# Power_Supply.net
KiCad netlist of a schematic drawn in Altium Designer
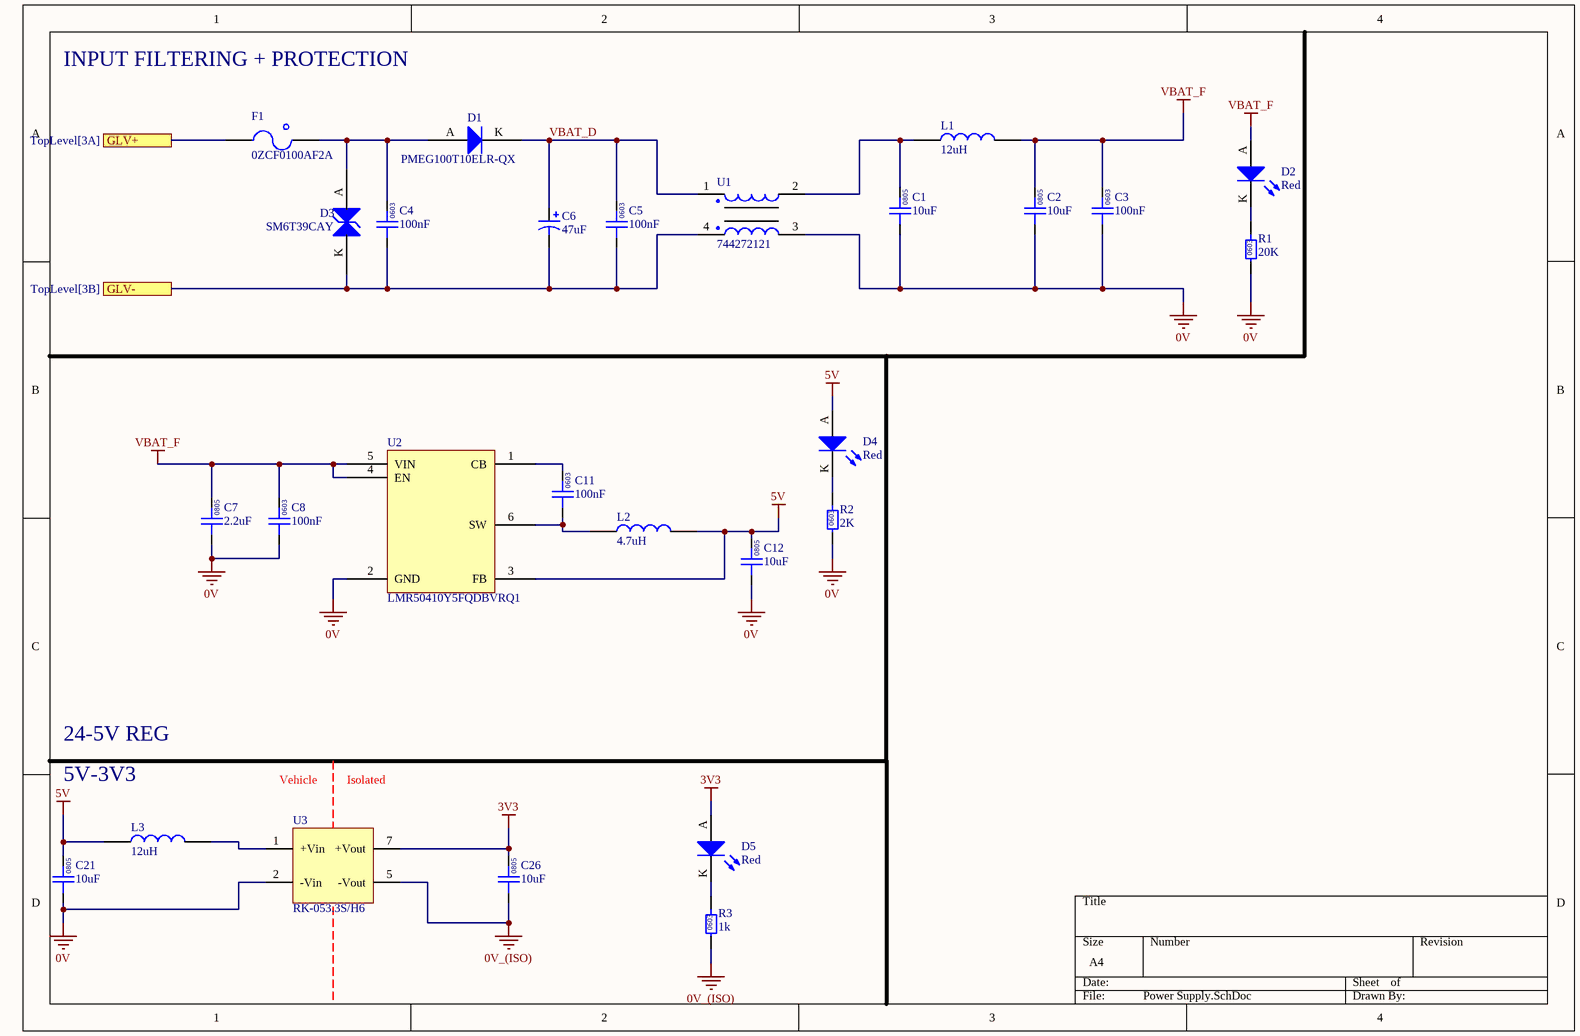
[diagram p0: Power Supply.SchDoc]

(export (version "E")
  (design (tool "Eeschema 10.0.6"))
  (components
    (comp (ref "C1")
      (value "10uF")
      (footprint "0805")
      (fields
        (field (name "PART NUMBER") "GRM21BR6YA106KE43L")
        (field (name "MANUFACTURER") "muRata")
        (field (name "TOLERANCE") "10%")
      )
      (libsource (lib "ts_standard_library") (part "Capacitor 0805"))
    )
    (comp (ref "C2")
      (value "10uF")
      (footprint "0805")
      (fields
        (field (name "PART NUMBER") "GRM21BR6YA106KE43L")
        (field (name "MANUFACTURER") "muRata")
        (field (name "TOLERANCE") "10%")
      )
      (libsource (lib "ts_standard_library") (part "Capacitor 0805"))
    )
    (comp (ref "C3")
      (value "100nF")
      (footprint "0603")
      (fields
        (field (name "PART NUMBER") "GCM188L81H104KA57D")
        (field (name "MANUFACTURER") "muRata")
        (field (name "TOLERANCE") "±10%")
      )
      (libsource (lib "ts_standard_library") (part "Capacitor 0603"))
    )
    (comp (ref "C4")
      (value "100nF")
      (footprint "0603")
      (fields
        (field (name "PART NUMBER") "GCM188L81H104KA57D")
        (field (name "MANUFACTURER") "muRata")
        (field (name "TOLERANCE") "±10%")
      )
      (libsource (lib "ts_standard_library") (part "Capacitor 0603"))
    )
    (comp (ref "C5")
      (value "100nF")
      (footprint "0603")
      (fields
        (field (name "PART NUMBER") "GCM188L81H104KA57D")
        (field (name "MANUFACTURER") "muRata")
        (field (name "TOLERANCE") "±10%")
      )
      (libsource (lib "ts_standard_library") (part "Capacitor 0603"))
    )
    (comp (ref "C6")
      (value "47uF")
      (footprint "CHEMI-CON ELCO")
      (fields (field (name "PART NUMBER") "HHXA350ARA470MF61G"))
      (libsource (lib "ts_standard_library") (part "Capacitor (Polarised)"))
    )
    (comp (ref "C7")
      (value "2.2uF")
      (footprint "0805")
      (fields
        (field (name "PART NUMBER") "GRM21BR61A226ME51L")
        (field (name "MANUFACTURER") "muRata")
        (field (name "TOLERANCE") "20%")
      )
      (libsource (lib "ts_standard_library") (part "Capacitor 0805"))
    )
    (comp (ref "C8")
      (value "100nF")
      (footprint "0603")
      (fields
        (field (name "PART NUMBER") "GCM188L81H104KA57D")
        (field (name "MANUFACTURER") "muRata")
        (field (name "TOLERANCE") "±10%")
      )
      (libsource (lib "ts_standard_library") (part "Capacitor 0603"))
    )
    (comp (ref "C11")
      (value "100nF")
      (footprint "0603")
      (fields
        (field (name "PART NUMBER") "GCM188L81H104KA57D")
        (field (name "MANUFACTURER") "muRata")
        (field (name "TOLERANCE") "±10%")
      )
      (libsource (lib "ts_standard_library") (part "Capacitor 0603"))
    )
    (comp (ref "C12")
      (value "10uF")
      (footprint "0805")
      (fields
        (field (name "PART NUMBER") "GRM21BR6YA106KE43L")
        (field (name "MANUFACTURER") "muRata")
        (field (name "TOLERANCE") "10%")
      )
      (libsource (lib "ts_standard_library") (part "Capacitor 0805"))
    )
    (comp (ref "C21")
      (value "10uF")
      (footprint "0805")
      (fields
        (field (name "PART NUMBER") "GRM21BR6YA106KE43L")
        (field (name "MANUFACTURER") "muRata")
        (field (name "TOLERANCE") "10%")
      )
      (libsource (lib "ts_standard_library") (part "Capacitor 0805"))
    )
    (comp (ref "C26")
      (value "10uF")
      (footprint "0805")
      (fields
        (field (name "PART NUMBER") "GRM21BR6YA106KE43L")
        (field (name "MANUFACTURER") "muRata")
        (field (name "TOLERANCE") "10%")
      )
      (libsource (lib "ts_standard_library") (part "Capacitor 0805"))
    )
    (comp (ref "D1")
      (value "PMEG100T10ELR-QX")
      (footprint "SODFL350X110-2N")
      (description "Diode 100 V 1A Surface Mount SOD-123W")
      (libsource (lib "Team Swinburne") (part "PMEG100T10ELR-QX"))
    )
    (comp (ref "D2")
      (value "Red")
      (footprint "0805 LED")
      (description "Red LED Indication - Discrete 1.75V 0805 (2012 Metric)")
      (fields (field (name "PART NUMBER") "SML-210LTT86") (field (name "MANUFACTURER") "ROHM Semiconductor"))
      (libsource (lib "ts_standard_library") (part "LED"))
    )
    (comp (ref "D3")
      (value "SM6T39CAY")
      (footprint "SM6T39CAY-Footprint-1")
      (description "TVS Diode Single Bi-Dir 33.3V 600W Automotive 2-Pin SMB T/R / TVS DIODE 33.3VWM 69.7VC SMB")
      (libsource (lib "Team Swinburne") (part "SM6T39CAY-Symbol"))
    )
    (comp (ref "D4")
      (value "Red")
      (footprint "0805 LED")
      (description "Red LED Indication - Discrete 1.75V 0805 (2012 Metric)")
      (fields (field (name "PART NUMBER") "SML-210LTT86") (field (name "MANUFACTURER") "ROHM Semiconductor"))
      (libsource (lib "ts_standard_library") (part "LED"))
    )
    (comp (ref "D5")
      (value "Red")
      (footprint "0805 LED")
      (description "Red LED Indication - Discrete 1.75V 0805 (2012 Metric)")
      (fields (field (name "PART NUMBER") "SML-210LTT86") (field (name "MANUFACTURER") "ROHM Semiconductor"))
      (libsource (lib "ts_standard_library") (part "LED"))
    )
    (comp (ref "F1")
      (value "0ZCF0100AF2A")
      (footprint "2920")
      (description "PTC RESET FUSE 60V 1A 292")
      (fields
        (field (name "MANUFACTURER") "Littelfuse Inc.")
        (field (name "DIGIKEY PART NUMBER") "507-2070-1-ND")
      )
      (libsource (lib "ts_standard_library") (part "PTC Fuse"))
    )
    (comp (ref "L1")
      (value "12uH")
      (footprint "1812")
      (fields
        (field (name "PART NUMBER") "RLS-126")
        (field (name "MANUFACTURER") "Recom")
        (field (name "TOLERANCE") "0.2")
      )
      (libsource (lib "ts_standard_library") (part "Inductor"))
    )
    (comp (ref "L2")
      (value "4.7uH")
      (footprint "SRN3015TA-4R7M")
      (fields
        (field (name "PART NUMBER") "SRN4018-4R7M")
        (field (name "MANUFACTURER") "Bourns")
        (field (name "TOLERANCE") "0.2")
      )
      (libsource (lib "ts_standard_library") (part "Inductor"))
    )
    (comp (ref "L3")
      (value "12uH")
      (footprint "1812")
      (fields
        (field (name "PART NUMBER") "RLS-126")
        (field (name "MANUFACTURER") "Recom")
        (field (name "TOLERANCE") "0.2")
      )
      (libsource (lib "ts_standard_library") (part "Inductor"))
    )
    (comp (ref "R1")
      (value "20K")
      (footprint "0603")
      (fields
        (field (name "PART NUMBER") "RC0603FR-0720KL")
        (field (name "MANUFACTURER") "YAGEO")
        (field (name "TOLERANCE") "0.01")
      )
      (libsource (lib "ts_standard_library") (part "Resistor 0603"))
    )
    (comp (ref "R2")
      (value "2K")
      (footprint "0603")
      (fields
        (field (name "PART NUMBER") "RC0603FR-072KL")
        (field (name "MANUFACTURER") "YAGEO")
        (field (name "TOLERANCE") "0.01")
      )
      (libsource (lib "ts_standard_library") (part "Resistor 0603"))
    )
    (comp (ref "R3")
      (value "1k")
      (footprint "0603")
      (fields
        (field (name "PART NUMBER") "RC0603FR-071KL")
        (field (name "MANUFACTURER") "YAGEO")
        (field (name "TOLERANCE") "0.01")
      )
      (libsource (lib "ts_standard_library") (part "Resistor 0603"))
    )
    (comp (ref "U1")
      (value "744272121")
      (footprint "Wurth 4-PC Pad")
      (fields
        (field (name "MANUFACTURER") "Wurth Electronics Inc")
        (field (name "DIGIKEY PART NUMBER") "732-1489-1-ND")
      )
      (libsource (lib "ts_standard_library") (part "CM Choke"))
    )
    (comp (ref "U2")
      (value "LMR50410Y5FQDBVRQ1")
      (footprint "TI-SOT23-6")
      (description "IC REG BUCK 5V 1A SOT23-6")
      (fields (field (name "PART NUMBER") "LMR50410-Q1") (field (name "MANUFACTURER") "Texas Instruments"))
      (libsource (lib "ts_standard_library") (part "LMR50410Y5FQDBVRQ1"))
    )
    (comp (ref "U3")
      (value "RK-053.3S/H6")
      (footprint "RK-053.3S/H6")
      (description "DC DC CONVERTER 3.3V 1W")
      (fields (field (name "MANUFACTURER") "Recom"))
      (libsource (lib "ts_standard_library") (part "RK-053.3S/H6"))
    )
  )
  (nets
    (net (code "1") (name "/GLV+") (class "Default")
      (node (ref "F1") (pin "1") (pinfunction "1_1") (pintype "passive"))
    )
    (net (code "2") (name "/GLV-") (class "Default")
      (node (ref "C4") (pin "1") (pinfunction "1_1") (pintype "passive"))
      (node (ref "C5") (pin "1") (pinfunction "1_1") (pintype "passive"))
      (node (ref "C6") (pin "1") (pinfunction "1_1") (pintype "passive"))
      (node (ref "D3") (pin "K") (pintype "passive"))
      (node (ref "U1") (pin "4") (pinfunction "4_4") (pintype "passive"))
    )
    (net (code "3") (name "/VBAT_D") (class "Default")
      (node (ref "C5") (pin "2") (pinfunction "2_2") (pintype "passive"))
      (node (ref "C6") (pin "2") (pinfunction "2_2") (pintype "passive"))
      (node (ref "D1") (pin "K") (pintype "passive"))
      (node (ref "U1") (pin "1") (pinfunction "1_1") (pintype "passive"))
    )
    (net (code "4") (name "0V") (class "Default")
      (node (ref "C1") (pin "1") (pinfunction "1_1") (pintype "passive"))
      (node (ref "C12") (pin "1") (pinfunction "1_1") (pintype "passive"))
      (node (ref "C2") (pin "1") (pinfunction "1_1") (pintype "passive"))
      (node (ref "C21") (pin "1") (pinfunction "1_1") (pintype "passive"))
      (node (ref "C3") (pin "1") (pinfunction "1_1") (pintype "passive"))
      (node (ref "C7") (pin "1") (pinfunction "1_1") (pintype "passive"))
      (node (ref "C8") (pin "1") (pinfunction "1_1") (pintype "passive"))
      (node (ref "R1") (pin "1") (pinfunction "1_1") (pintype "passive"))
      (node (ref "R2") (pin "1") (pinfunction "1_1") (pintype "passive"))
      (node (ref "U1") (pin "3") (pinfunction "3_3") (pintype "power_in"))
      (node (ref "U2") (pin "2") (pinfunction "GND_2") (pintype "passive"))
      (node (ref "U3") (pin "2") (pinfunction "-Vin_2") (pintype "power_in"))
    )
    (net (code "5") (name "0V_(ISO)") (class "Default")
      (node (ref "C26") (pin "1") (pinfunction "1_1") (pintype "passive"))
      (node (ref "R3") (pin "1") (pinfunction "1_1") (pintype "passive"))
      (node (ref "U3") (pin "5") (pinfunction "-Vout_5") (pintype "power_in"))
    )
    (net (code "6") (name "3V3") (class "Default")
      (node (ref "C26") (pin "2") (pinfunction "2_2") (pintype "passive"))
      (node (ref "D5") (pin "A") (pinfunction "A_A") (pintype "passive"))
      (node (ref "U3") (pin "7") (pinfunction "+Vout_7") (pintype "power_in"))
    )
    (net (code "7") (name "5V") (class "Default")
      (node (ref "C12") (pin "2") (pinfunction "2_2") (pintype "passive"))
      (node (ref "C21") (pin "2") (pinfunction "2_2") (pintype "passive"))
      (node (ref "D4") (pin "A") (pinfunction "A_A") (pintype "passive"))
      (node (ref "L2") (pin "1") (pinfunction "1_1") (pintype "passive"))
      (node (ref "L3") (pin "2") (pinfunction "2_2") (pintype "passive"))
      (node (ref "U2") (pin "3") (pinfunction "FB_3") (pintype "passive"))
    )
    (net (code "8") (name "Net-(C1-Pad2)") (class "Default")
      (node (ref "C1") (pin "2") (pinfunction "2_2") (pintype "passive"))
      (node (ref "L1") (pin "2") (pinfunction "2_2") (pintype "passive"))
      (node (ref "U1") (pin "2") (pinfunction "2_2") (pintype "passive"))
    )
    (net (code "9") (name "Net-(C4-Pad2)") (class "Default")
      (node (ref "C4") (pin "2") (pinfunction "2_2") (pintype "passive"))
      (node (ref "D1") (pin "A") (pintype "passive"))
      (node (ref "D3") (pin "A") (pintype "passive"))
      (node (ref "F1") (pin "2") (pinfunction "2_2") (pintype "passive"))
    )
    (net (code "10") (name "Net-(D2-PadK)") (class "Default")
      (node (ref "D2") (pin "K") (pinfunction "K_K") (pintype "passive"))
      (node (ref "R1") (pin "2") (pinfunction "2_2") (pintype "passive"))
    )
    (net (code "11") (name "Net-(D4-PadK)") (class "Default")
      (node (ref "D4") (pin "K") (pinfunction "K_K") (pintype "passive"))
      (node (ref "R2") (pin "2") (pinfunction "2_2") (pintype "passive"))
    )
    (net (code "12") (name "Net-(D5-PadK)") (class "Default")
      (node (ref "D5") (pin "K") (pinfunction "K_K") (pintype "passive"))
      (node (ref "R3") (pin "2") (pinfunction "2_2") (pintype "passive"))
    )
    (net (code "13") (name "Net-(U2-CB)") (class "Default")
      (node (ref "C11") (pin "2") (pinfunction "2_2") (pintype "passive"))
      (node (ref "U2") (pin "1") (pinfunction "CB_1") (pintype "passive"))
    )
    (net (code "14") (name "Net-(U2-SW)") (class "Default")
      (node (ref "C11") (pin "1") (pinfunction "1_1") (pintype "passive"))
      (node (ref "L2") (pin "2") (pinfunction "2_2") (pintype "passive"))
      (node (ref "U2") (pin "6") (pinfunction "SW_6") (pintype "passive"))
    )
    (net (code "15") (name "Net-(U3-+Vin)") (class "Default")
      (node (ref "L3") (pin "1") (pinfunction "1_1") (pintype "passive"))
      (node (ref "U3") (pin "1") (pinfunction "+Vin_1") (pintype "power_in"))
    )
    (net (code "16") (name "VBAT_F") (class "Default")
      (node (ref "C2") (pin "2") (pinfunction "2_2") (pintype "passive"))
      (node (ref "C3") (pin "2") (pinfunction "2_2") (pintype "passive"))
      (node (ref "C7") (pin "2") (pinfunction "2_2") (pintype "passive"))
      (node (ref "C8") (pin "2") (pinfunction "2_2") (pintype "passive"))
      (node (ref "D2") (pin "A") (pinfunction "A_A") (pintype "passive"))
      (node (ref "L1") (pin "1") (pinfunction "1_1") (pintype "passive"))
      (node (ref "U2") (pin "4") (pinfunction "EN_4") (pintype "passive"))
      (node (ref "U2") (pin "5") (pinfunction "VIN_5") (pintype "passive"))
    )
  )
)
